# S88WirelessSender.net
KiCad netlist of a schematic drawn in EAGLE
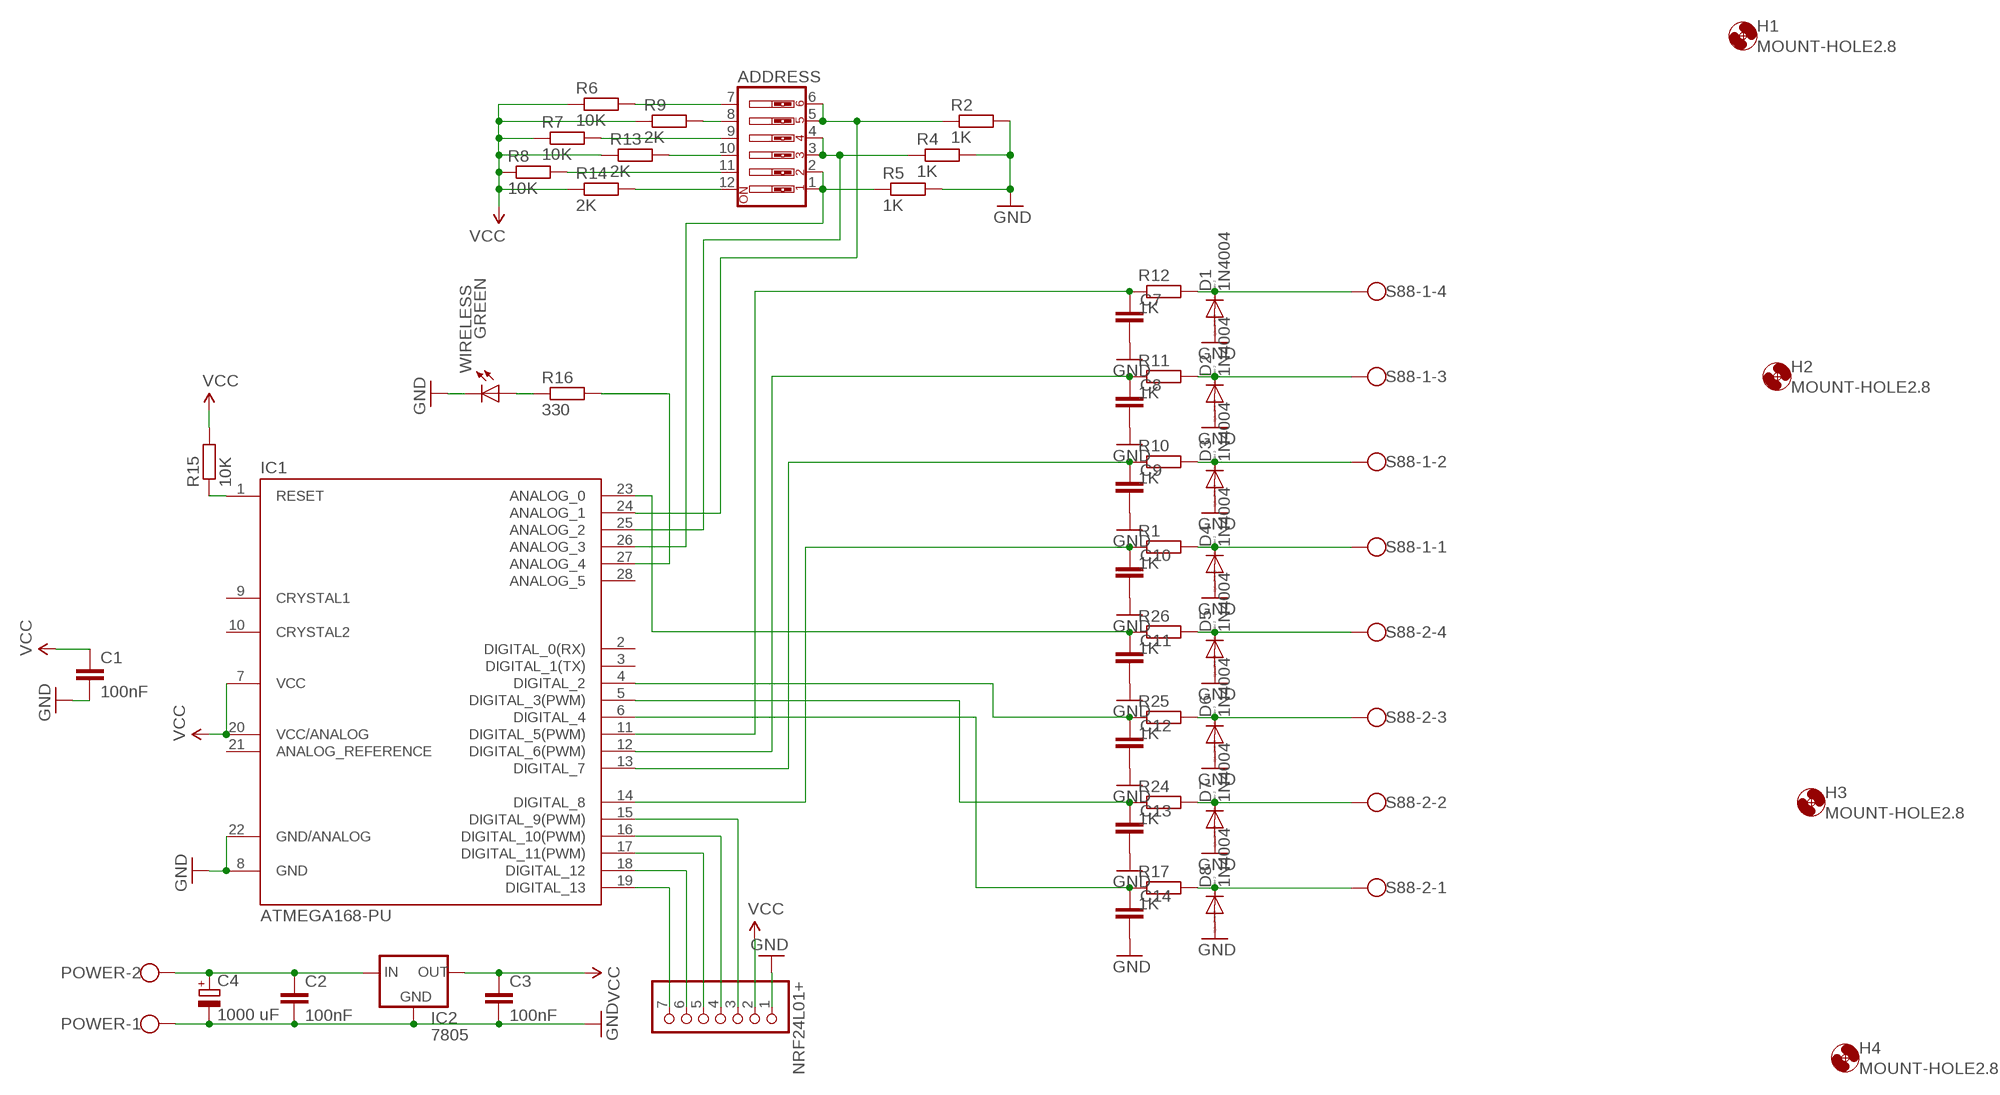
[diagram p0: schematic, sheet 1]

(export (version "E")
  (design (tool "Eeschema 10.0.6"))
  (components
    (comp (ref "ADDRESS")
      (value "SW_DIP-6")
      (footprint "eagle-import:EDG-06")
      (libsource (lib "eagle-import") (part "SW_DIP-6"))
    )
    (comp (ref "C1")
      (value "100nF")
      (footprint "eagle-import:C025-030X050")
      (libsource (lib "eagle-import") (part "C-EU025-030X050"))
    )
    (comp (ref "C2")
      (value "100nF")
      (footprint "eagle-import:C025-030X050")
      (libsource (lib "eagle-import") (part "C-EU025-030X050"))
    )
    (comp (ref "C3")
      (value "100nF")
      (footprint "eagle-import:C025-030X050")
      (libsource (lib "eagle-import") (part "C-EU025-030X050"))
    )
    (comp (ref "C4")
      (value "1000 uF")
      (footprint "eagle-import:E5-13")
      (libsource (lib "eagle-import") (part "CPOL-EUE5-13"))
    )
    (comp (ref "C7")
      (value "C-EU025-024X044")
      (footprint "eagle-import:C025-024X044")
      (libsource (lib "eagle-import") (part "C-EU025-024X044"))
    )
    (comp (ref "C8")
      (value "C-EU025-024X044")
      (footprint "eagle-import:C025-024X044")
      (libsource (lib "eagle-import") (part "C-EU025-024X044"))
    )
    (comp (ref "C9")
      (value "C-EU025-024X044")
      (footprint "eagle-import:C025-024X044")
      (libsource (lib "eagle-import") (part "C-EU025-024X044"))
    )
    (comp (ref "C10")
      (value "C-EU025-024X044")
      (footprint "eagle-import:C025-024X044")
      (libsource (lib "eagle-import") (part "C-EU025-024X044"))
    )
    (comp (ref "C11")
      (value "C-EU025-024X044")
      (footprint "eagle-import:C025-024X044")
      (libsource (lib "eagle-import") (part "C-EU025-024X044"))
    )
    (comp (ref "C12")
      (value "C-EU025-024X044")
      (footprint "eagle-import:C025-024X044")
      (libsource (lib "eagle-import") (part "C-EU025-024X044"))
    )
    (comp (ref "C13")
      (value "C-EU025-024X044")
      (footprint "eagle-import:C025-024X044")
      (libsource (lib "eagle-import") (part "C-EU025-024X044"))
    )
    (comp (ref "C14")
      (value "C-EU025-024X044")
      (footprint "eagle-import:C025-024X044")
      (libsource (lib "eagle-import") (part "C-EU025-024X044"))
    )
    (comp (ref "D1")
      (value "1N4004")
      (footprint "eagle-import:DO41-10")
      (libsource (lib "eagle-import") (part "1N4004"))
    )
    (comp (ref "D2")
      (value "1N4004")
      (footprint "eagle-import:DO41-10")
      (libsource (lib "eagle-import") (part "1N4004"))
    )
    (comp (ref "D3")
      (value "1N4004")
      (footprint "eagle-import:DO41-10")
      (libsource (lib "eagle-import") (part "1N4004"))
    )
    (comp (ref "D4")
      (value "1N4004")
      (footprint "eagle-import:DO41-10")
      (libsource (lib "eagle-import") (part "1N4004"))
    )
    (comp (ref "D5")
      (value "1N4004")
      (footprint "eagle-import:DO41-10")
      (libsource (lib "eagle-import") (part "1N4004"))
    )
    (comp (ref "D6")
      (value "1N4004")
      (footprint "eagle-import:DO41-10")
      (libsource (lib "eagle-import") (part "1N4004"))
    )
    (comp (ref "D7")
      (value "1N4004")
      (footprint "eagle-import:DO41-10")
      (libsource (lib "eagle-import") (part "1N4004"))
    )
    (comp (ref "D8")
      (value "1N4004")
      (footprint "eagle-import:DO41-10")
      (libsource (lib "eagle-import") (part "1N4004"))
    )
    (comp (ref "H1")
      (value "MOUNT-HOLE2.8")
      (footprint "eagle-import:2,8")
      (libsource (lib "eagle-import") (part "MOUNT-HOLE2.8"))
    )
    (comp (ref "H2")
      (value "MOUNT-HOLE2.8")
      (footprint "eagle-import:2,8")
      (libsource (lib "eagle-import") (part "MOUNT-HOLE2.8"))
    )
    (comp (ref "H3")
      (value "MOUNT-HOLE2.8")
      (footprint "eagle-import:2,8")
      (libsource (lib "eagle-import") (part "MOUNT-HOLE2.8"))
    )
    (comp (ref "H4")
      (value "MOUNT-HOLE2.8")
      (footprint "eagle-import:2,8")
      (libsource (lib "eagle-import") (part "MOUNT-HOLE2.8"))
    )
    (comp (ref "IC1")
      (value "ATMEGA168-PU")
      (footprint "eagle-import:DIL28-3")
      (libsource (lib "eagle-import") (part "ATMEGA168-PU"))
    )
    (comp (ref "IC2")
      (value "7805")
      (footprint "eagle-import:78XXS")
      (libsource (lib "eagle-import") (part "78XXS"))
    )
    (comp (ref "NRF24L01+")
      (value "PINHD-1X7")
      (footprint "eagle-import:1X07")
      (libsource (lib "eagle-import") (part "PINHD-1X7"))
    )
    (comp (ref "POWER")
      (value "W237-102")
      (footprint "eagle-import:W237-102")
      (fields (field (name "MPN") "237-102"))
      (libsource (lib "eagle-import") (part "W237-102"))
    )
    (comp (ref "R1")
      (value "1K")
      (footprint "eagle-import:0204_7")
      (libsource (lib "eagle-import") (part "R-EU_0204/7"))
    )
    (comp (ref "R2")
      (value "1K")
      (footprint "eagle-import:0204_7")
      (libsource (lib "eagle-import") (part "R-EU_0204/7"))
    )
    (comp (ref "R4")
      (value "1K")
      (footprint "eagle-import:0204_7")
      (libsource (lib "eagle-import") (part "R-EU_0204/7"))
    )
    (comp (ref "R5")
      (value "1K")
      (footprint "eagle-import:0204_7")
      (libsource (lib "eagle-import") (part "R-EU_0204/7"))
    )
    (comp (ref "R6")
      (value "10K")
      (footprint "eagle-import:0204V")
      (libsource (lib "eagle-import") (part "resistor_R-EU_0204/2V"))
    )
    (comp (ref "R7")
      (value "10K")
      (footprint "eagle-import:0204V")
      (libsource (lib "eagle-import") (part "resistor_R-EU_0204/2V"))
    )
    (comp (ref "R8")
      (value "10K")
      (footprint "eagle-import:0204V")
      (libsource (lib "eagle-import") (part "resistor_R-EU_0204/2V"))
    )
    (comp (ref "R9")
      (value "2K")
      (footprint "eagle-import:0204V")
      (libsource (lib "eagle-import") (part "resistor_R-EU_0204/2V"))
    )
    (comp (ref "R10")
      (value "1K")
      (footprint "eagle-import:0204_7")
      (libsource (lib "eagle-import") (part "R-EU_0204/7"))
    )
    (comp (ref "R11")
      (value "1K")
      (footprint "eagle-import:0204_7")
      (libsource (lib "eagle-import") (part "R-EU_0204/7"))
    )
    (comp (ref "R12")
      (value "1K")
      (footprint "eagle-import:0204_7")
      (libsource (lib "eagle-import") (part "R-EU_0204/7"))
    )
    (comp (ref "R13")
      (value "2K")
      (footprint "eagle-import:0204V")
      (libsource (lib "eagle-import") (part "resistor_R-EU_0204/2V"))
    )
    (comp (ref "R14")
      (value "2K")
      (footprint "eagle-import:0204V")
      (libsource (lib "eagle-import") (part "resistor_R-EU_0204/2V"))
    )
    (comp (ref "R15")
      (value "10K")
      (footprint "eagle-import:0204V")
      (libsource (lib "eagle-import") (part "resistor_R-EU_0204/2V"))
    )
    (comp (ref "R16")
      (value "330")
      (footprint "eagle-import:0204V")
      (libsource (lib "eagle-import") (part "resistor_R-EU_0204/2V"))
    )
    (comp (ref "R17")
      (value "1K")
      (footprint "eagle-import:0204_7")
      (libsource (lib "eagle-import") (part "R-EU_0204/7"))
    )
    (comp (ref "R24")
      (value "1K")
      (footprint "eagle-import:0204_7")
      (libsource (lib "eagle-import") (part "R-EU_0204/7"))
    )
    (comp (ref "R25")
      (value "1K")
      (footprint "eagle-import:0204_7")
      (libsource (lib "eagle-import") (part "R-EU_0204/7"))
    )
    (comp (ref "R26")
      (value "1K")
      (footprint "eagle-import:0204_7")
      (libsource (lib "eagle-import") (part "R-EU_0204/7"))
    )
    (comp (ref "S88-1")
      (value "W237-4")
      (footprint "eagle-import:W237-4")
      (libsource (lib "eagle-import") (part "W237-4"))
    )
    (comp (ref "S88-2")
      (value "W237-4")
      (footprint "eagle-import:W237-4")
      (libsource (lib "eagle-import") (part "W237-4"))
    )
    (comp (ref "WIRELESS")
      (value "GREEN")
      (footprint "eagle-import:LED3MM")
      (libsource (lib "eagle-import") (part "LED3MM"))
    )
  )
  (nets
    (net (code "1") (name "GND") (class "Default")
      (node (ref "C1") (pin "2") (pinfunction "2_2") (pintype "passive"))
      (node (ref "C10") (pin "2") (pinfunction "2_2") (pintype "passive"))
      (node (ref "C11") (pin "2") (pinfunction "2_2") (pintype "passive"))
      (node (ref "C12") (pin "2") (pinfunction "2_2") (pintype "passive"))
      (node (ref "C13") (pin "2") (pinfunction "2_2") (pintype "passive"))
      (node (ref "C14") (pin "2") (pinfunction "2_2") (pintype "passive"))
      (node (ref "C2") (pin "2") (pinfunction "2_2") (pintype "passive"))
      (node (ref "C3") (pin "2") (pinfunction "2_2") (pintype "passive"))
      (node (ref "C4") (pin "-") (pinfunction "-_-") (pintype "passive"))
      (node (ref "C7") (pin "2") (pinfunction "2_2") (pintype "passive"))
      (node (ref "C8") (pin "2") (pinfunction "2_2") (pintype "passive"))
      (node (ref "C9") (pin "2") (pinfunction "2_2") (pintype "passive"))
      (node (ref "D1") (pin "A") (pinfunction "A_A") (pintype "passive"))
      (node (ref "D2") (pin "A") (pinfunction "A_A") (pintype "passive"))
      (node (ref "D3") (pin "A") (pinfunction "A_A") (pintype "passive"))
      (node (ref "D4") (pin "A") (pinfunction "A_A") (pintype "passive"))
      (node (ref "D5") (pin "A") (pinfunction "A_A") (pintype "passive"))
      (node (ref "D6") (pin "A") (pinfunction "A_A") (pintype "passive"))
      (node (ref "D7") (pin "A") (pinfunction "A_A") (pintype "passive"))
      (node (ref "D8") (pin "A") (pinfunction "A_A") (pintype "passive"))
      (node (ref "IC1") (pin "22") (pinfunction "GND/ANALOG_22") (pintype "power_in"))
      (node (ref "IC1") (pin "8") (pinfunction "GND_8") (pintype "power_in"))
      (node (ref "IC2") (pin "GND") (pinfunction "GND_GND") (pintype "input"))
      (node (ref "NRF24L01+") (pin "1") (pinfunction "1_1") (pintype "passive"))
      (node (ref "POWER") (pin "1") (pinfunction "KL_1") (pintype "passive"))
      (node (ref "R2") (pin "2") (pinfunction "2_2") (pintype "passive"))
      (node (ref "R4") (pin "2") (pinfunction "2_2") (pintype "passive"))
      (node (ref "R5") (pin "2") (pinfunction "2_2") (pintype "passive"))
      (node (ref "WIRELESS") (pin "K") (pinfunction "C_K") (pintype "passive"))
    )
    (net (code "2") (name "Net-(ADDRESS-Pad7)") (class "Default")
      (node (ref "ADDRESS") (pin "7") (pinfunction "7_7") (pintype "passive"))
      (node (ref "R6") (pin "2") (pinfunction "2_2") (pintype "passive"))
    )
    (net (code "3") (name "Net-(ADDRESS-Pad8)") (class "Default")
      (node (ref "ADDRESS") (pin "8") (pinfunction "8_8") (pintype "passive"))
      (node (ref "R9") (pin "2") (pinfunction "2_2") (pintype "passive"))
    )
    (net (code "4") (name "Net-(ADDRESS-Pad9)") (class "Default")
      (node (ref "ADDRESS") (pin "9") (pinfunction "9_9") (pintype "passive"))
      (node (ref "R7") (pin "2") (pinfunction "2_2") (pintype "passive"))
    )
    (net (code "5") (name "Net-(ADDRESS-Pad10)") (class "Default")
      (node (ref "ADDRESS") (pin "10") (pinfunction "10_10") (pintype "passive"))
      (node (ref "R13") (pin "2") (pinfunction "2_2") (pintype "passive"))
    )
    (net (code "6") (name "Net-(ADDRESS-Pad11)") (class "Default")
      (node (ref "ADDRESS") (pin "11") (pinfunction "11_11") (pintype "passive"))
      (node (ref "R8") (pin "2") (pinfunction "2_2") (pintype "passive"))
    )
    (net (code "7") (name "Net-(ADDRESS-Pad12)") (class "Default")
      (node (ref "ADDRESS") (pin "12") (pinfunction "12_12") (pintype "passive"))
      (node (ref "R14") (pin "2") (pinfunction "2_2") (pintype "passive"))
    )
    (net (code "8") (name "Net-(IC1-ANALOG_0)") (class "Default")
      (node (ref "C11") (pin "1") (pinfunction "1_1") (pintype "passive"))
      (node (ref "IC1") (pin "23") (pinfunction "ANALOG_0_23") (pintype "bidirectional"))
      (node (ref "R26") (pin "1") (pinfunction "1_1") (pintype "passive"))
    )
    (net (code "9") (name "Net-(IC1-ANALOG_1)") (class "Default")
      (node (ref "ADDRESS") (pin "5") (pinfunction "5_5") (pintype "passive"))
      (node (ref "ADDRESS") (pin "6") (pinfunction "6_6") (pintype "passive"))
      (node (ref "IC1") (pin "24") (pinfunction "ANALOG_1_24") (pintype "bidirectional"))
      (node (ref "R2") (pin "1") (pinfunction "1_1") (pintype "passive"))
    )
    (net (code "10") (name "Net-(IC1-ANALOG_2)") (class "Default")
      (node (ref "ADDRESS") (pin "3") (pinfunction "3_3") (pintype "passive"))
      (node (ref "ADDRESS") (pin "4") (pinfunction "4_4") (pintype "passive"))
      (node (ref "IC1") (pin "25") (pinfunction "ANALOG_2_25") (pintype "bidirectional"))
      (node (ref "R4") (pin "1") (pinfunction "1_1") (pintype "passive"))
    )
    (net (code "11") (name "Net-(IC1-ANALOG_3)") (class "Default")
      (node (ref "ADDRESS") (pin "1") (pinfunction "1_1") (pintype "passive"))
      (node (ref "ADDRESS") (pin "2") (pinfunction "2_2") (pintype "passive"))
      (node (ref "IC1") (pin "26") (pinfunction "ANALOG_3_26") (pintype "bidirectional"))
      (node (ref "R5") (pin "1") (pinfunction "1_1") (pintype "passive"))
    )
    (net (code "12") (name "Net-(IC1-ANALOG_4)") (class "Default")
      (node (ref "IC1") (pin "27") (pinfunction "ANALOG_4_27") (pintype "bidirectional"))
      (node (ref "R16") (pin "2") (pinfunction "2_2") (pintype "passive"))
    )
    (net (code "13") (name "Net-(IC1-DIGITAL_2)") (class "Default")
      (node (ref "C12") (pin "1") (pinfunction "1_1") (pintype "passive"))
      (node (ref "IC1") (pin "4") (pinfunction "DIGITAL_2_4") (pintype "bidirectional"))
      (node (ref "R25") (pin "1") (pinfunction "1_1") (pintype "passive"))
    )
    (net (code "14") (name "Net-(IC1-DIGITAL_3(PWM))") (class "Default")
      (node (ref "C13") (pin "1") (pinfunction "1_1") (pintype "passive"))
      (node (ref "IC1") (pin "5") (pinfunction "DIGITAL_3(PWM)_5") (pintype "bidirectional"))
      (node (ref "R24") (pin "1") (pinfunction "1_1") (pintype "passive"))
    )
    (net (code "15") (name "Net-(IC1-DIGITAL_4)") (class "Default")
      (node (ref "C14") (pin "1") (pinfunction "1_1") (pintype "passive"))
      (node (ref "IC1") (pin "6") (pinfunction "DIGITAL_4_6") (pintype "bidirectional"))
      (node (ref "R17") (pin "1") (pinfunction "1_1") (pintype "passive"))
    )
    (net (code "16") (name "Net-(IC1-DIGITAL_5(PWM))") (class "Default")
      (node (ref "C7") (pin "1") (pinfunction "1_1") (pintype "passive"))
      (node (ref "IC1") (pin "11") (pinfunction "DIGITAL_5(PWM)_11") (pintype "bidirectional"))
      (node (ref "R12") (pin "1") (pinfunction "1_1") (pintype "passive"))
    )
    (net (code "17") (name "Net-(IC1-DIGITAL_6(PWM))") (class "Default")
      (node (ref "C8") (pin "1") (pinfunction "1_1") (pintype "passive"))
      (node (ref "IC1") (pin "12") (pinfunction "DIGITAL_6(PWM)_12") (pintype "bidirectional"))
      (node (ref "R11") (pin "1") (pinfunction "1_1") (pintype "passive"))
    )
    (net (code "18") (name "Net-(IC1-DIGITAL_7)") (class "Default")
      (node (ref "C9") (pin "1") (pinfunction "1_1") (pintype "passive"))
      (node (ref "IC1") (pin "13") (pinfunction "DIGITAL_7_13") (pintype "bidirectional"))
      (node (ref "R10") (pin "1") (pinfunction "1_1") (pintype "passive"))
    )
    (net (code "19") (name "Net-(IC1-DIGITAL_8)") (class "Default")
      (node (ref "C10") (pin "1") (pinfunction "1_1") (pintype "passive"))
      (node (ref "IC1") (pin "14") (pinfunction "DIGITAL_8_14") (pintype "bidirectional"))
      (node (ref "R1") (pin "1") (pinfunction "1_1") (pintype "passive"))
    )
    (net (code "20") (name "Net-(IC1-DIGITAL_9(PWM))") (class "Default")
      (node (ref "IC1") (pin "15") (pinfunction "DIGITAL_9(PWM)_15") (pintype "bidirectional"))
      (node (ref "NRF24L01+") (pin "3") (pinfunction "3_3") (pintype "passive"))
    )
    (net (code "21") (name "Net-(IC1-DIGITAL_10(PWM))") (class "Default")
      (node (ref "IC1") (pin "16") (pinfunction "DIGITAL_10(PWM)_16") (pintype "bidirectional"))
      (node (ref "NRF24L01+") (pin "4") (pinfunction "4_4") (pintype "passive"))
    )
    (net (code "22") (name "Net-(IC1-DIGITAL_11(PWM))") (class "Default")
      (node (ref "IC1") (pin "17") (pinfunction "DIGITAL_11(PWM)_17") (pintype "bidirectional"))
      (node (ref "NRF24L01+") (pin "5") (pinfunction "5_5") (pintype "passive"))
    )
    (net (code "23") (name "Net-(IC1-DIGITAL_12)") (class "Default")
      (node (ref "IC1") (pin "18") (pinfunction "DIGITAL_12_18") (pintype "bidirectional"))
      (node (ref "NRF24L01+") (pin "6") (pinfunction "6_6") (pintype "passive"))
    )
    (net (code "24") (name "Net-(IC1-DIGITAL_13)") (class "Default")
      (node (ref "IC1") (pin "19") (pinfunction "DIGITAL_13_19") (pintype "bidirectional"))
      (node (ref "NRF24L01+") (pin "7") (pinfunction "7_7") (pintype "passive"))
    )
    (net (code "25") (name "Net-(IC1-RESET)") (class "Default")
      (node (ref "IC1") (pin "1") (pinfunction "RESET_1") (pintype "bidirectional"))
      (node (ref "R15") (pin "1") (pinfunction "1_1") (pintype "passive"))
    )
    (net (code "26") (name "Net-(POWERB-KL)") (class "Default")
      (node (ref "C2") (pin "1") (pinfunction "1_1") (pintype "passive"))
      (node (ref "C4") (pin "+") (pinfunction "+_+") (pintype "passive"))
      (node (ref "IC2") (pin "IN") (pinfunction "IN_IN") (pintype "input"))
      (node (ref "POWER") (pin "2") (pinfunction "KL_2") (pintype "passive"))
    )
    (net (code "27") (name "Net-(R16-Pad1)") (class "Default")
      (node (ref "R16") (pin "1") (pinfunction "1_1") (pintype "passive"))
      (node (ref "WIRELESS") (pin "A") (pinfunction "A_A") (pintype "passive"))
    )
    (net (code "28") (name "Net-(S88-1A-KL)") (class "Default")
      (node (ref "D4") (pin "C") (pinfunction "C_C") (pintype "passive"))
      (node (ref "R1") (pin "2") (pinfunction "2_2") (pintype "passive"))
      (node (ref "S88-1") (pin "1") (pinfunction "KL_1") (pintype "passive"))
    )
    (net (code "29") (name "Net-(S88-1B-KL)") (class "Default")
      (node (ref "D3") (pin "C") (pinfunction "C_C") (pintype "passive"))
      (node (ref "R10") (pin "2") (pinfunction "2_2") (pintype "passive"))
      (node (ref "S88-1") (pin "2") (pinfunction "KL_2") (pintype "passive"))
    )
    (net (code "30") (name "Net-(S88-1C-KL)") (class "Default")
      (node (ref "D2") (pin "C") (pinfunction "C_C") (pintype "passive"))
      (node (ref "R11") (pin "2") (pinfunction "2_2") (pintype "passive"))
      (node (ref "S88-1") (pin "3") (pinfunction "KL_3") (pintype "passive"))
    )
    (net (code "31") (name "Net-(S88-1D-KL)") (class "Default")
      (node (ref "D1") (pin "C") (pinfunction "C_C") (pintype "passive"))
      (node (ref "R12") (pin "2") (pinfunction "2_2") (pintype "passive"))
      (node (ref "S88-1") (pin "4") (pinfunction "KL_4") (pintype "passive"))
    )
    (net (code "32") (name "Net-(S88-2A-KL)") (class "Default")
      (node (ref "D8") (pin "C") (pinfunction "C_C") (pintype "passive"))
      (node (ref "R17") (pin "2") (pinfunction "2_2") (pintype "passive"))
      (node (ref "S88-2") (pin "1") (pinfunction "KL_1") (pintype "passive"))
    )
    (net (code "33") (name "Net-(S88-2B-KL)") (class "Default")
      (node (ref "D7") (pin "C") (pinfunction "C_C") (pintype "passive"))
      (node (ref "R24") (pin "2") (pinfunction "2_2") (pintype "passive"))
      (node (ref "S88-2") (pin "2") (pinfunction "KL_2") (pintype "passive"))
    )
    (net (code "34") (name "Net-(S88-2C-KL)") (class "Default")
      (node (ref "D6") (pin "C") (pinfunction "C_C") (pintype "passive"))
      (node (ref "R25") (pin "2") (pinfunction "2_2") (pintype "passive"))
      (node (ref "S88-2") (pin "3") (pinfunction "KL_3") (pintype "passive"))
    )
    (net (code "35") (name "Net-(S88-2D-KL)") (class "Default")
      (node (ref "D5") (pin "C") (pinfunction "C_C") (pintype "passive"))
      (node (ref "R26") (pin "2") (pinfunction "2_2") (pintype "passive"))
      (node (ref "S88-2") (pin "4") (pinfunction "KL_4") (pintype "passive"))
    )
    (net (code "36") (name "VCC") (class "Default")
      (node (ref "C1") (pin "1") (pinfunction "1_1") (pintype "passive"))
      (node (ref "C3") (pin "1") (pinfunction "1_1") (pintype "passive"))
      (node (ref "IC1") (pin "20") (pinfunction "VCC/ANALOG_20") (pintype "passive"))
      (node (ref "IC1") (pin "7") (pinfunction "VCC_7") (pintype "power_in"))
      (node (ref "IC2") (pin "OUT") (pinfunction "OUT_OUT") (pintype "passive"))
      (node (ref "NRF24L01+") (pin "2") (pinfunction "2_2") (pintype "passive"))
      (node (ref "R13") (pin "1") (pinfunction "1_1") (pintype "passive"))
      (node (ref "R14") (pin "1") (pinfunction "1_1") (pintype "passive"))
      (node (ref "R15") (pin "2") (pinfunction "2_2") (pintype "passive"))
      (node (ref "R6") (pin "1") (pinfunction "1_1") (pintype "passive"))
      (node (ref "R7") (pin "1") (pinfunction "1_1") (pintype "passive"))
      (node (ref "R8") (pin "1") (pinfunction "1_1") (pintype "passive"))
      (node (ref "R9") (pin "1") (pinfunction "1_1") (pintype "passive"))
    )
    (net (code "37") (name "unconnected-(IC1-ANALOG_5-Pad28)") (class "Default")
      (node (ref "IC1") (pin "28") (pinfunction "ANALOG_5_28") (pintype "bidirectional"))
    )
    (net (code "38") (name "unconnected-(IC1-ANALOG_REFERENCE-Pad21)") (class "Default")
      (node (ref "IC1") (pin "21") (pinfunction "ANALOG_REFERENCE_21") (pintype "passive"))
    )
    (net (code "39") (name "unconnected-(IC1-CRYSTAL1-Pad9)") (class "Default")
      (node (ref "IC1") (pin "9") (pinfunction "CRYSTAL1_9") (pintype "bidirectional"))
    )
    (net (code "40") (name "unconnected-(IC1-CRYSTAL2-Pad10)") (class "Default")
      (node (ref "IC1") (pin "10") (pinfunction "CRYSTAL2_10") (pintype "bidirectional"))
    )
    (net (code "41") (name "unconnected-(IC1-DIGITAL_0(RX)-Pad2)") (class "Default")
      (node (ref "IC1") (pin "2") (pinfunction "DIGITAL_0(RX)_2") (pintype "bidirectional"))
    )
    (net (code "42") (name "unconnected-(IC1-DIGITAL_1(TX)-Pad3)") (class "Default")
      (node (ref "IC1") (pin "3") (pinfunction "DIGITAL_1(TX)_3") (pintype "bidirectional"))
    )
  )
)
